# PowerBoard.net
KiCad netlist of a schematic drawn in EAGLE
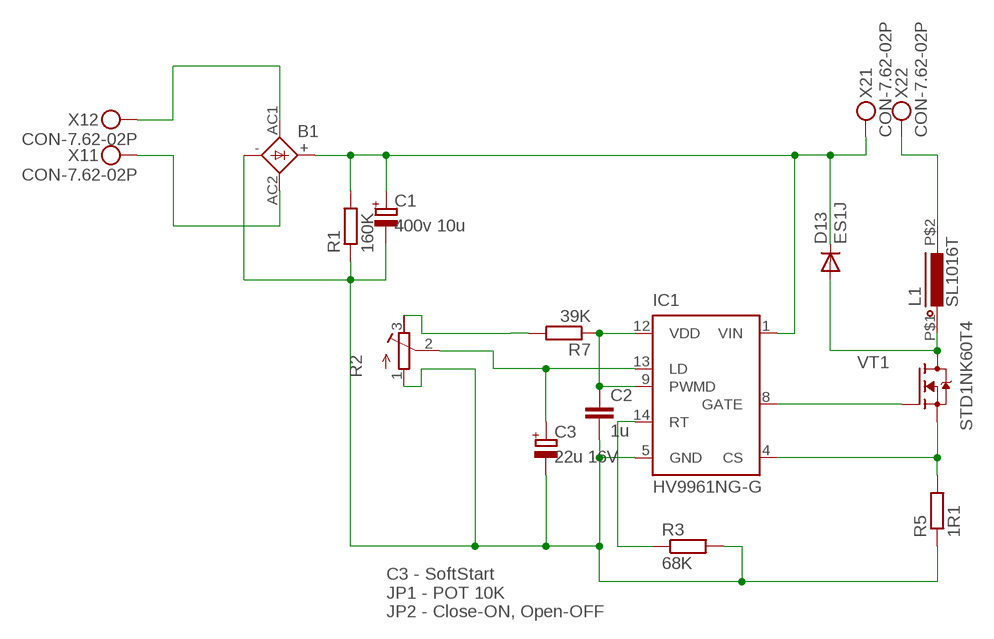
[diagram p0: schematic, sheet 1]

(export (version "E")
  (design (tool "Eeschema 10.0.6"))
  (components
    (comp (ref "B1")
      (value "BRIDGEDBS")
      (footprint "eagle-import:DBS")
      (libsource (lib "eagle-import") (part "BRIDGEDBS"))
    )
    (comp (ref "C1")
      (value "400v 10u")
      (footprint "eagle-import:E3,5-8")
      (libsource (lib "eagle-import") (part "CAP-POL_E3.5-8"))
    )
    (comp (ref "C2")
      (value "1u")
      (footprint "eagle-import:CAP0805")
      (libsource (lib "eagle-import") (part "CAP_0805"))
    )
    (comp (ref "C3")
      (value "22u 16V")
      (footprint "eagle-import:CT3528")
      (libsource (lib "eagle-import") (part "CAP-POL_3528"))
    )
    (comp (ref "D13")
      (value "ES1J")
      (footprint "eagle-import:DO214AC")
      (libsource (lib "eagle-import") (part "DIODE_ES1J"))
    )
    (comp (ref "IC1")
      (value "HV9961NG-G")
      (footprint "eagle-import:SOIC-16NG")
      (libsource (lib "eagle-import") (part "HV9910BNG"))
    )
    (comp (ref "L1")
      (value "SL1016T")
      (footprint "eagle-import:SL1016")
      (libsource (lib "eagle-import") (part "INDUCTORSL1016"))
    )
    (comp (ref "R1")
      (value "160K")
      (footprint "eagle-import:MF-0125")
      (libsource (lib "eagle-import") (part "R_MF-0125"))
    )
    (comp (ref "R2")
      (value "R_POT3296X")
      (footprint "eagle-import:POT-3296X")
      (libsource (lib "eagle-import") (part "R_POT3296X"))
    )
    (comp (ref "R3")
      (value "68K")
      (footprint "eagle-import:RESC2012X50")
      (libsource (lib "eagle-import") (part "R_R0805"))
    )
    (comp (ref "R5")
      (value "1R1")
      (footprint "eagle-import:MF-05")
      (libsource (lib "eagle-import") (part "R_MF-05"))
    )
    (comp (ref "R7")
      (value "39K")
      (footprint "eagle-import:RESC2012X50")
      (libsource (lib "eagle-import") (part "R_R0805"))
    )
    (comp (ref "VT1")
      (value "STD1NK60T4")
      (footprint "eagle-import:DPAK")
      (libsource (lib "eagle-import") (part "FET-NDPAK"))
    )
    (comp (ref "X1")
      (value "CON-7.62-02P")
      (footprint "eagle-import:KF25C-7.62-02P-13")
      (libsource (lib "eagle-import") (part "CON-7.62-02P"))
    )
    (comp (ref "X2")
      (value "CON-7.62-02P")
      (footprint "eagle-import:KF25C-7.62-02P-13")
      (libsource (lib "eagle-import") (part "CON-7.62-02P"))
    )
  )
  (nets
    (net (code "1") (name "Net-(IC1-CS)") (class "Default")
      (node (ref "IC1") (pin "4") (pinfunction "CS_4") (pintype "input"))
      (node (ref "R5") (pin "2") (pinfunction "2_2") (pintype "passive"))
      (node (ref "VT1") (pin "S") (pinfunction "S_S") (pintype "passive"))
    )
    (net (code "2") (name "Net-(IC1-GATE)") (class "Default")
      (node (ref "IC1") (pin "8") (pinfunction "GATE_8") (pintype "output"))
      (node (ref "VT1") (pin "G") (pinfunction "G_G") (pintype "passive"))
    )
    (net (code "3") (name "Net-(IC1-GND)") (class "Default")
      (node (ref "B1") (pin "-") (pinfunction "-_-") (pintype "passive"))
      (node (ref "C1") (pin "-") (pinfunction "-_-") (pintype "passive"))
      (node (ref "C2") (pin "2") (pinfunction "2_2") (pintype "passive"))
      (node (ref "C3") (pin "-") (pinfunction "-_-") (pintype "passive"))
      (node (ref "IC1") (pin "5") (pinfunction "GND_5") (pintype "power_in"))
      (node (ref "R1") (pin "1") (pinfunction "1_1") (pintype "passive"))
      (node (ref "R2") (pin "1") (pinfunction "A_1") (pintype "passive"))
      (node (ref "R3") (pin "2") (pinfunction "2_2") (pintype "passive"))
      (node (ref "R5") (pin "1") (pinfunction "1_1") (pintype "passive"))
    )
    (net (code "4") (name "Net-(IC1-LD)") (class "Default")
      (node (ref "C3") (pin "+") (pinfunction "+_+") (pintype "passive"))
      (node (ref "IC1") (pin "13") (pinfunction "LD_13") (pintype "input"))
      (node (ref "R2") (pin "2") (pinfunction "S_2") (pintype "passive"))
    )
    (net (code "5") (name "Net-(IC1-PWMD)") (class "Default")
      (node (ref "C2") (pin "1") (pinfunction "1_1") (pintype "passive"))
      (node (ref "IC1") (pin "12") (pinfunction "VDD_12") (pintype "power_in"))
      (node (ref "IC1") (pin "9") (pinfunction "PWMD_9") (pintype "input"))
      (node (ref "R7") (pin "1") (pinfunction "1_1") (pintype "passive"))
    )
    (net (code "6") (name "Net-(IC1-RT)") (class "Default")
      (node (ref "IC1") (pin "14") (pinfunction "RT_14") (pintype "passive"))
      (node (ref "R3") (pin "1") (pinfunction "1_1") (pintype "passive"))
    )
    (net (code "7") (name "Net-(IC1-VIN)") (class "Default")
      (node (ref "B1") (pin "+") (pinfunction "+_+") (pintype "passive"))
      (node (ref "C1") (pin "+") (pinfunction "+_+") (pintype "passive"))
      (node (ref "D13") (pin "C") (pinfunction "C_C") (pintype "passive"))
      (node (ref "IC1") (pin "1") (pinfunction "VIN_1") (pintype "input"))
      (node (ref "R1") (pin "2") (pinfunction "2_2") (pintype "passive"))
      (node (ref "X2") (pin "P$1") (pinfunction "KL_P$1") (pintype "passive"))
    )
    (net (code "8") (name "Net-(L1-1)") (class "Default")
      (node (ref "D13") (pin "A") (pinfunction "A_A") (pintype "passive"))
      (node (ref "L1") (pin "P$1") (pinfunction "1_P$1") (pintype "passive"))
      (node (ref "VT1") (pin "D") (pinfunction "D_D") (pintype "passive"))
    )
    (net (code "9") (name "Net-(L1-2)") (class "Default")
      (node (ref "L1") (pin "P$2") (pinfunction "2_P$2") (pintype "passive"))
      (node (ref "X2") (pin "P$2") (pinfunction "KL_P$2") (pintype "passive"))
    )
    (net (code "10") (name "Net-(R2-E)") (class "Default")
      (node (ref "R2") (pin "3") (pinfunction "E_3") (pintype "passive"))
      (node (ref "R7") (pin "2") (pinfunction "2_2") (pintype "passive"))
    )
    (net (code "11") (name "Net-(X1A-KL)") (class "Default")
      (node (ref "B1") (pin "AC2") (pinfunction "AC2_AC2") (pintype "passive"))
      (node (ref "X1") (pin "P$1") (pinfunction "KL_P$1") (pintype "passive"))
    )
    (net (code "12") (name "Net-(X1B-KL)") (class "Default")
      (node (ref "B1") (pin "AC1") (pinfunction "AC1_AC1") (pintype "passive"))
      (node (ref "X1") (pin "P$2") (pinfunction "KL_P$2") (pintype "passive"))
    )
  )
)
